# ETHERNET.net
KiCad netlist of a schematic drawn in Altium Designer
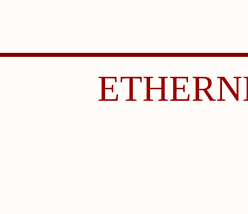
[diagram p0: ETHERNET.SchDoc, top left]
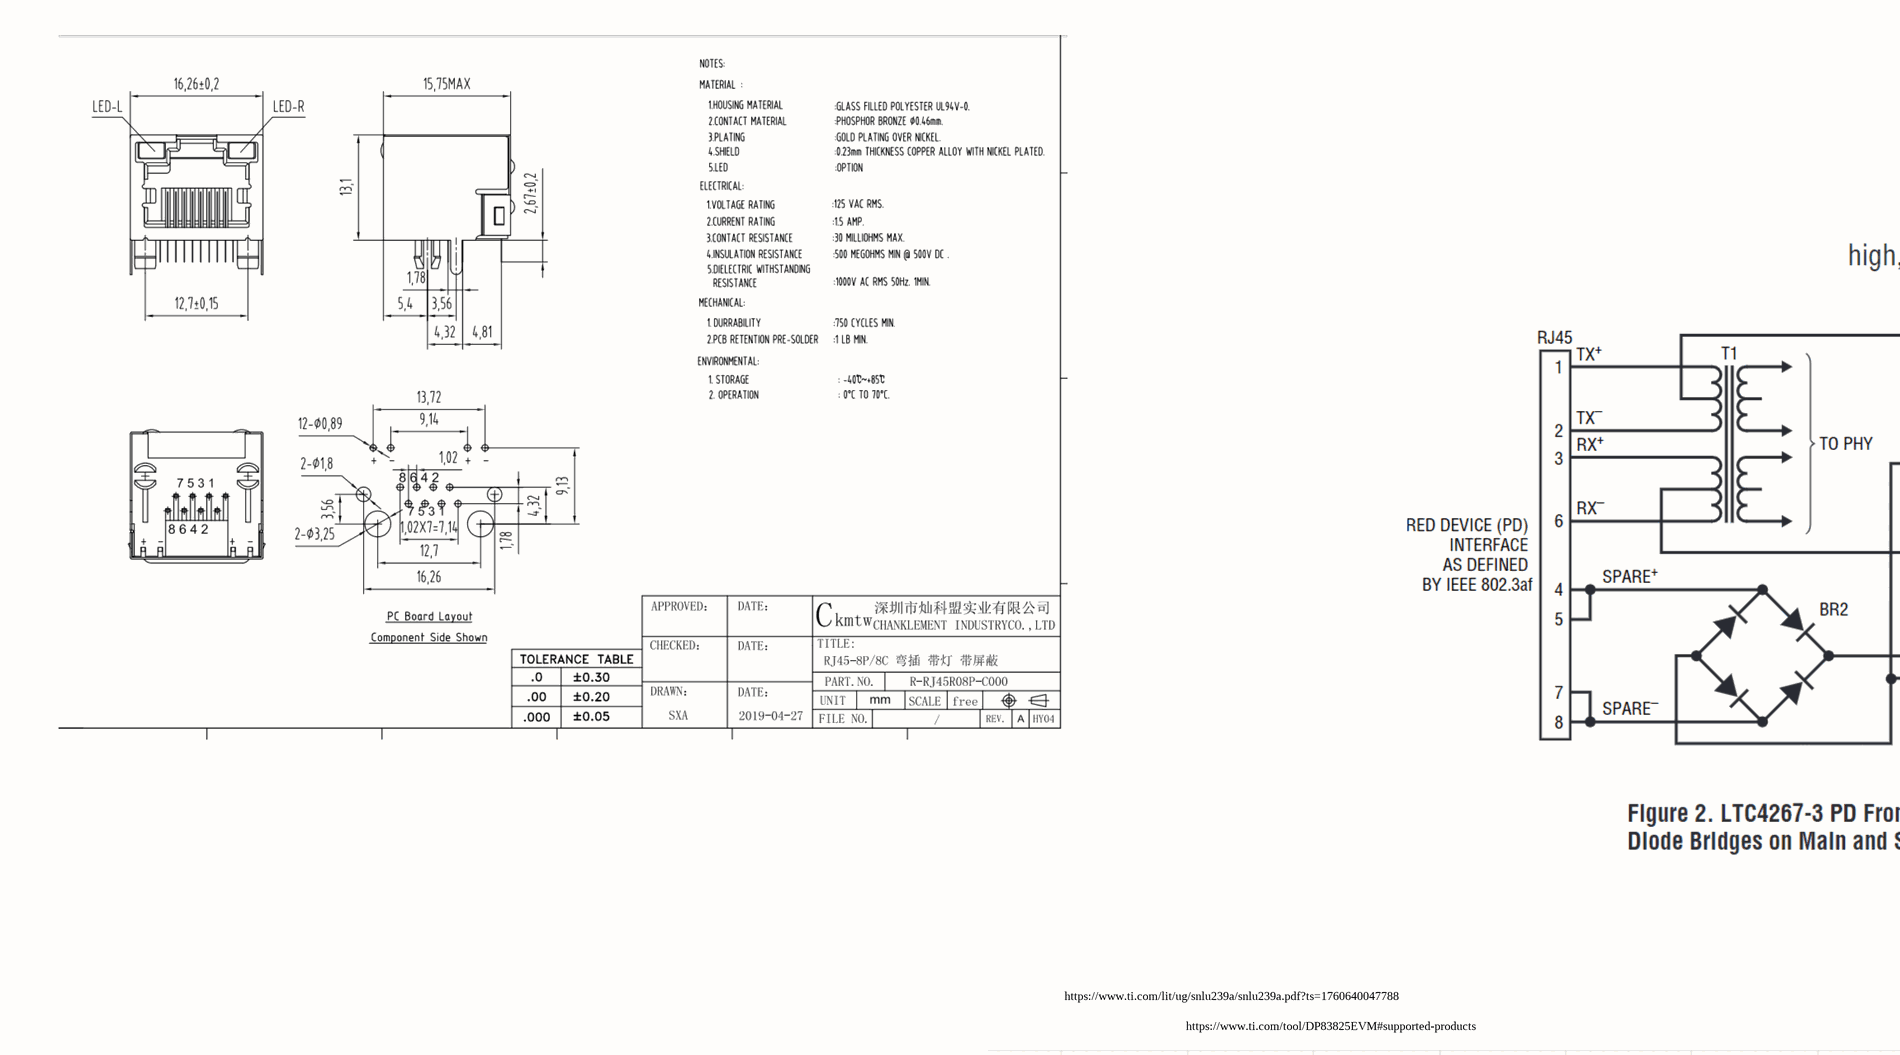
[diagram p1: ETHERNET.SchDoc, top middle]
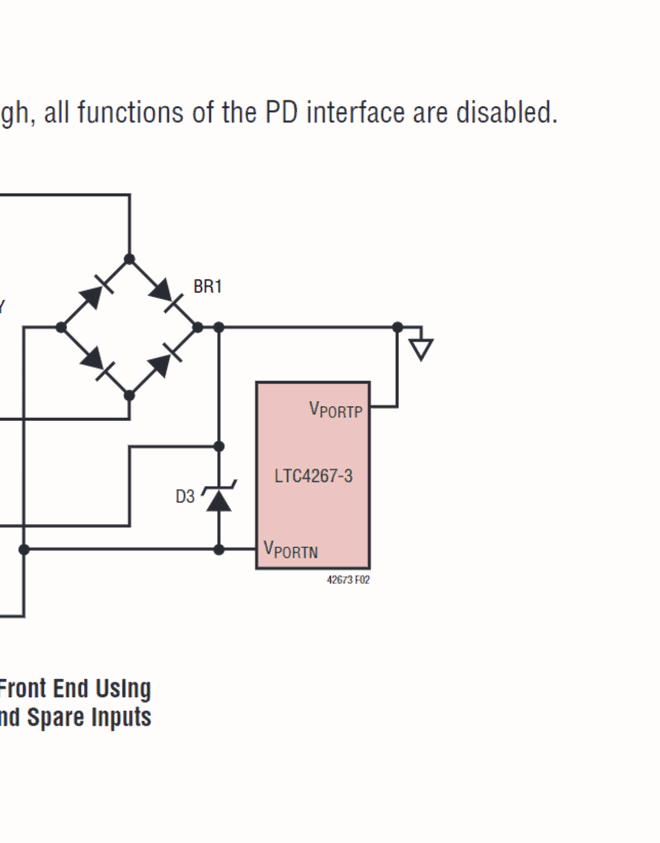
[diagram p2: ETHERNET.SchDoc, top right]
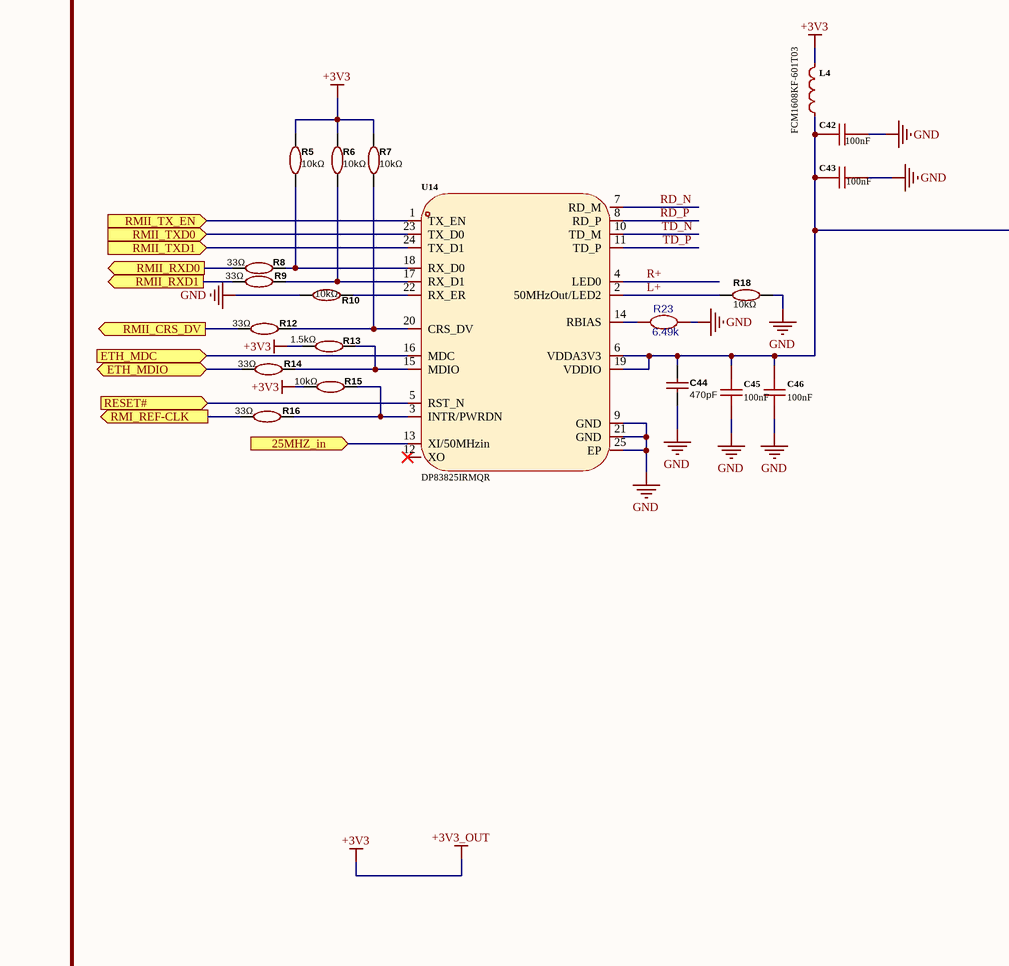
[diagram p3: ETHERNET.SchDoc, centre left]
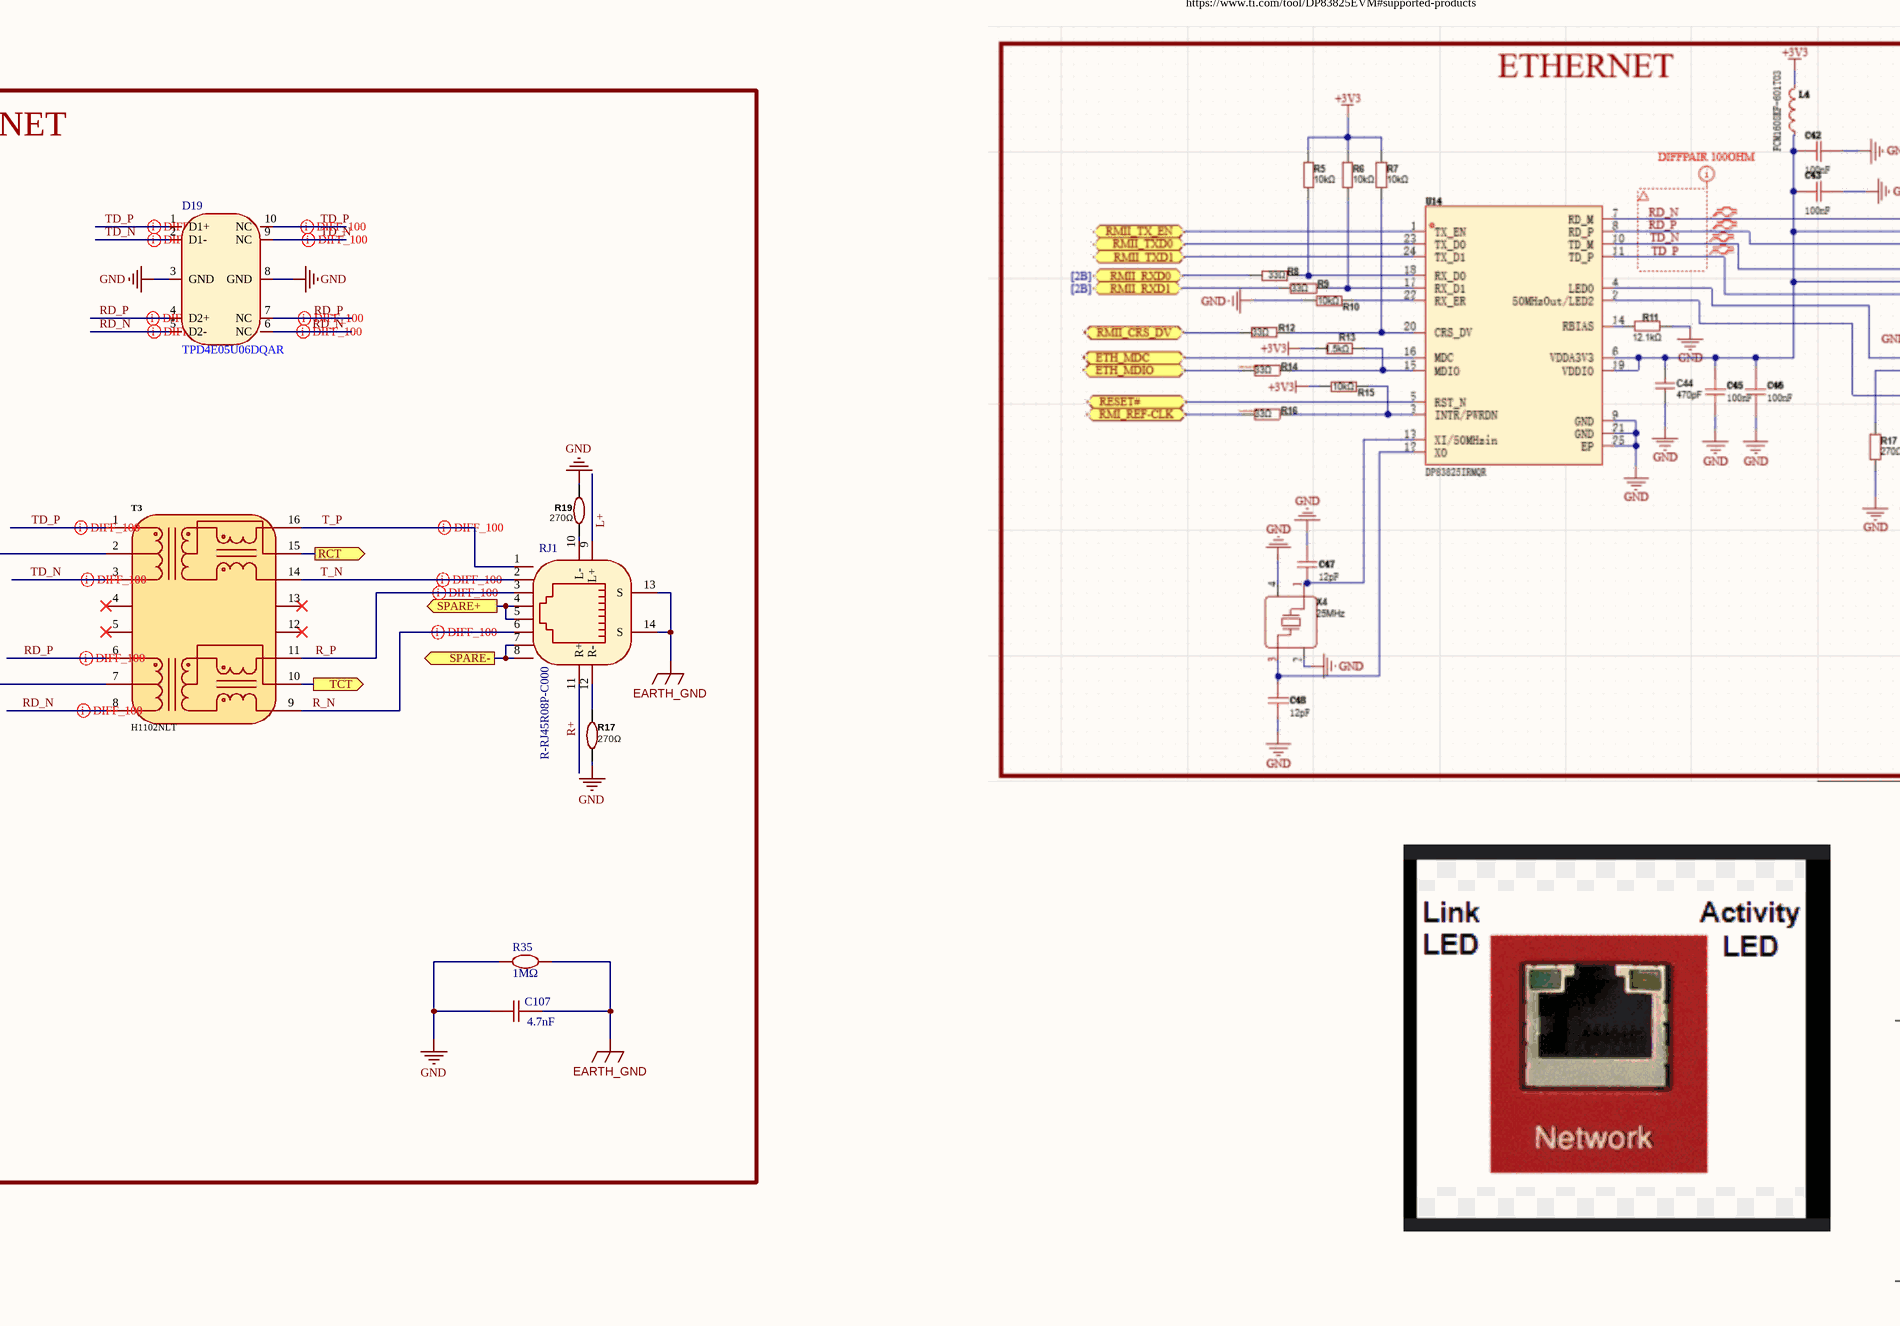
[diagram p4: ETHERNET.SchDoc, centre middle]
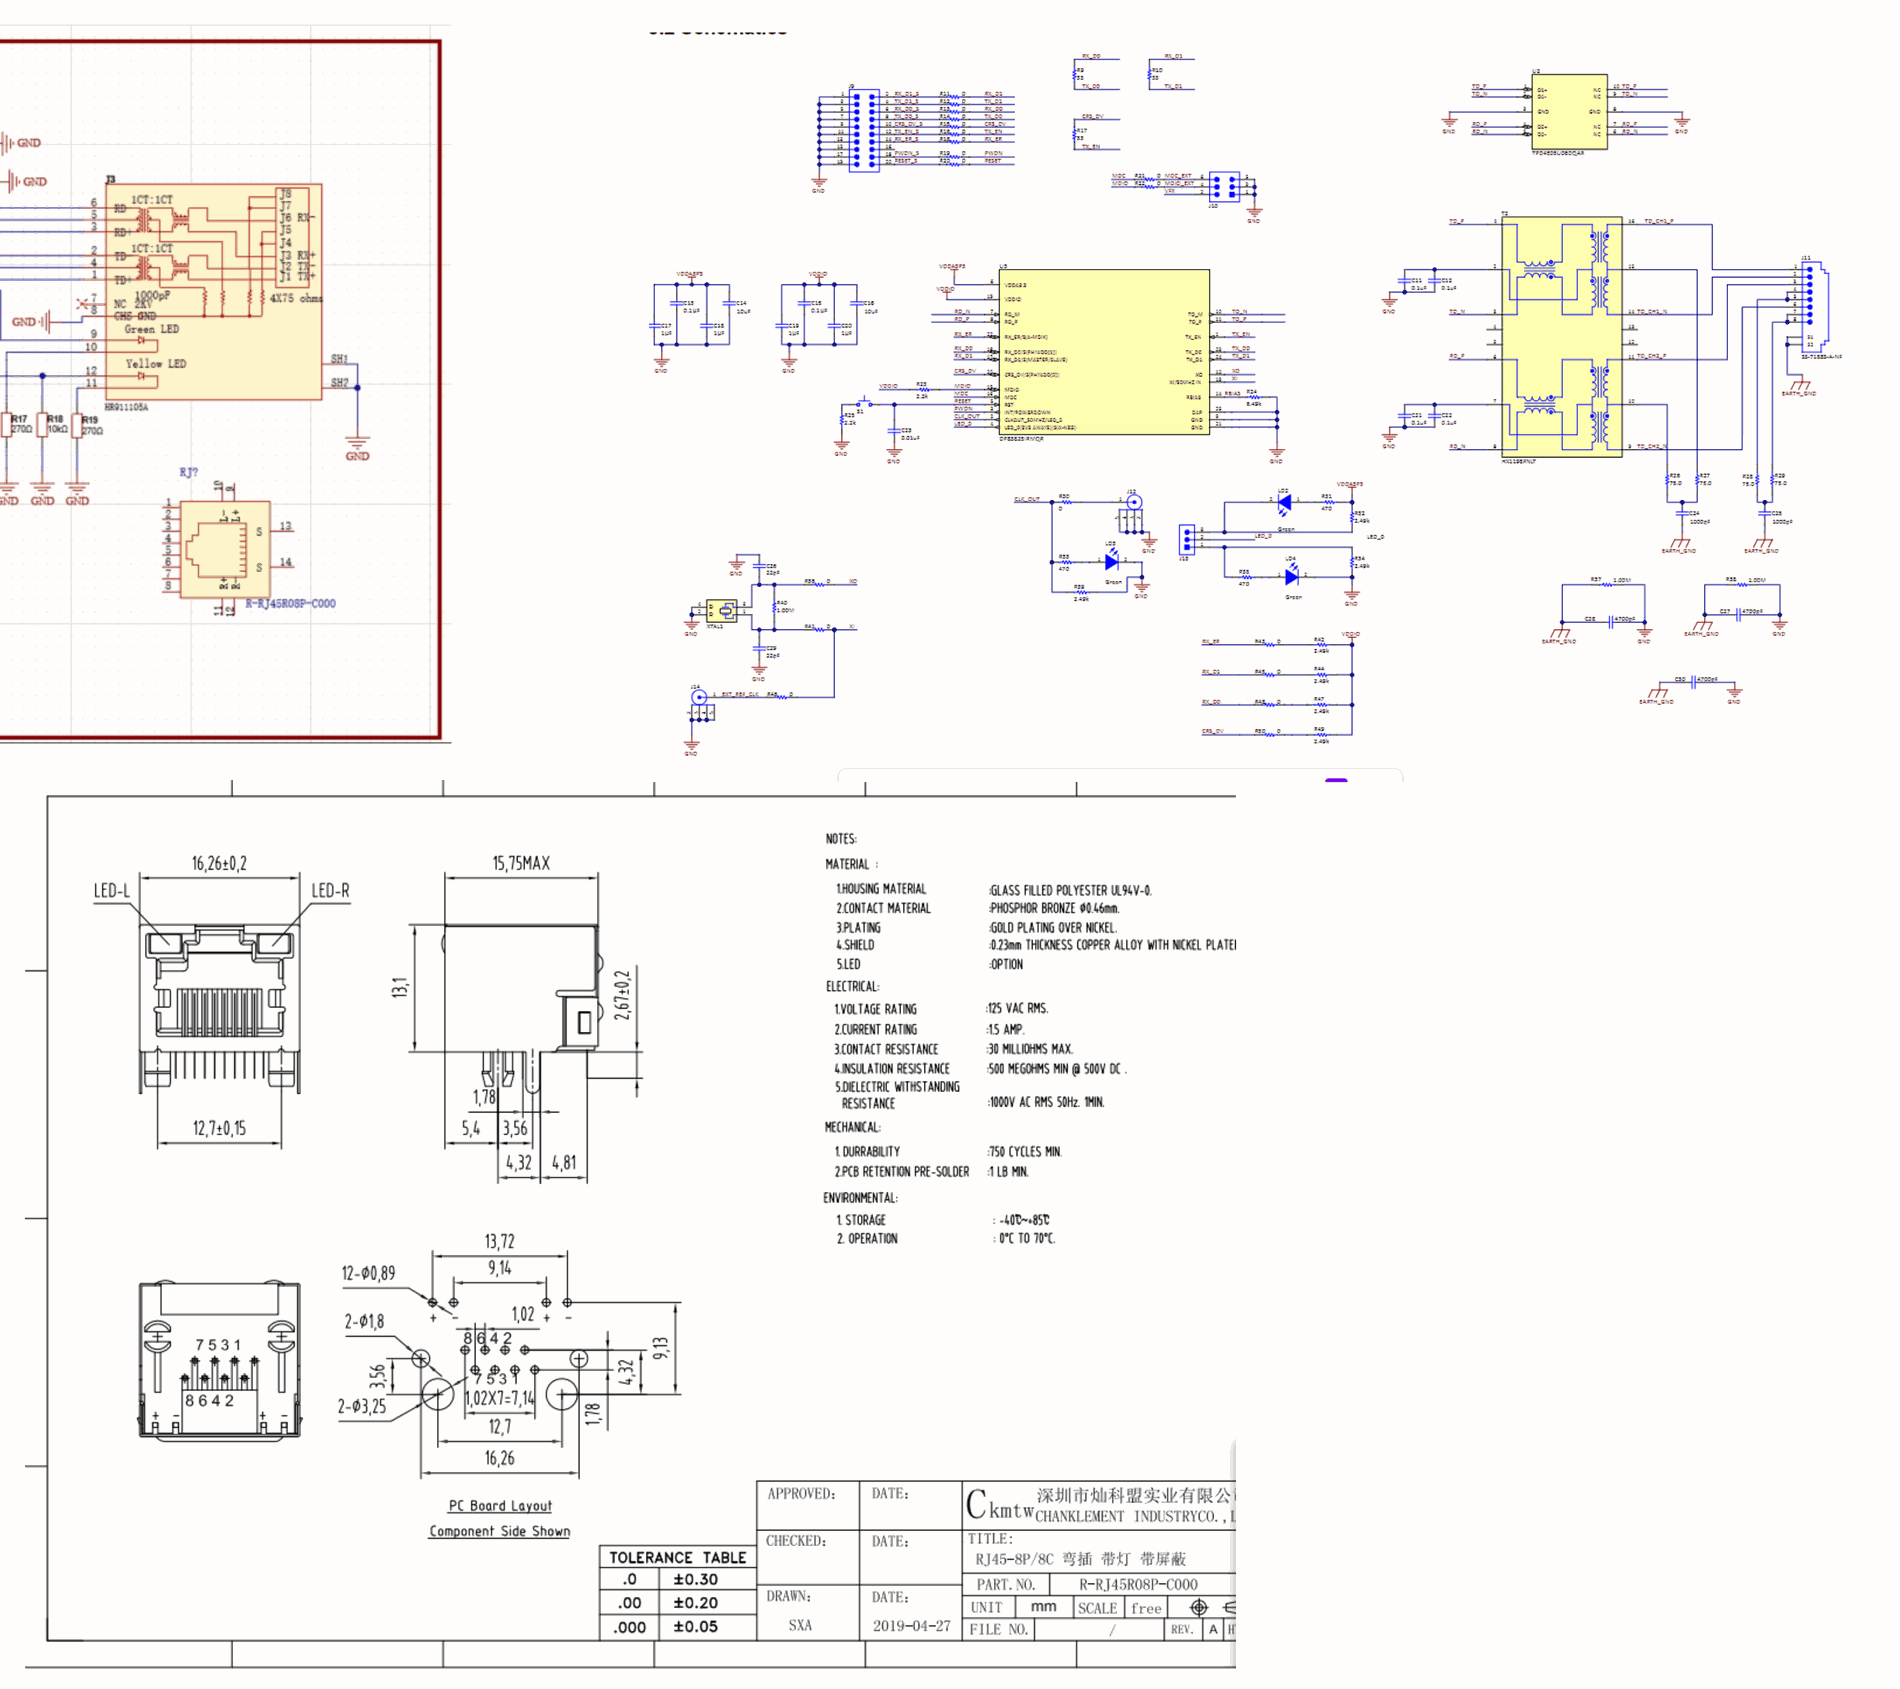
[diagram p5: ETHERNET.SchDoc, centre right]
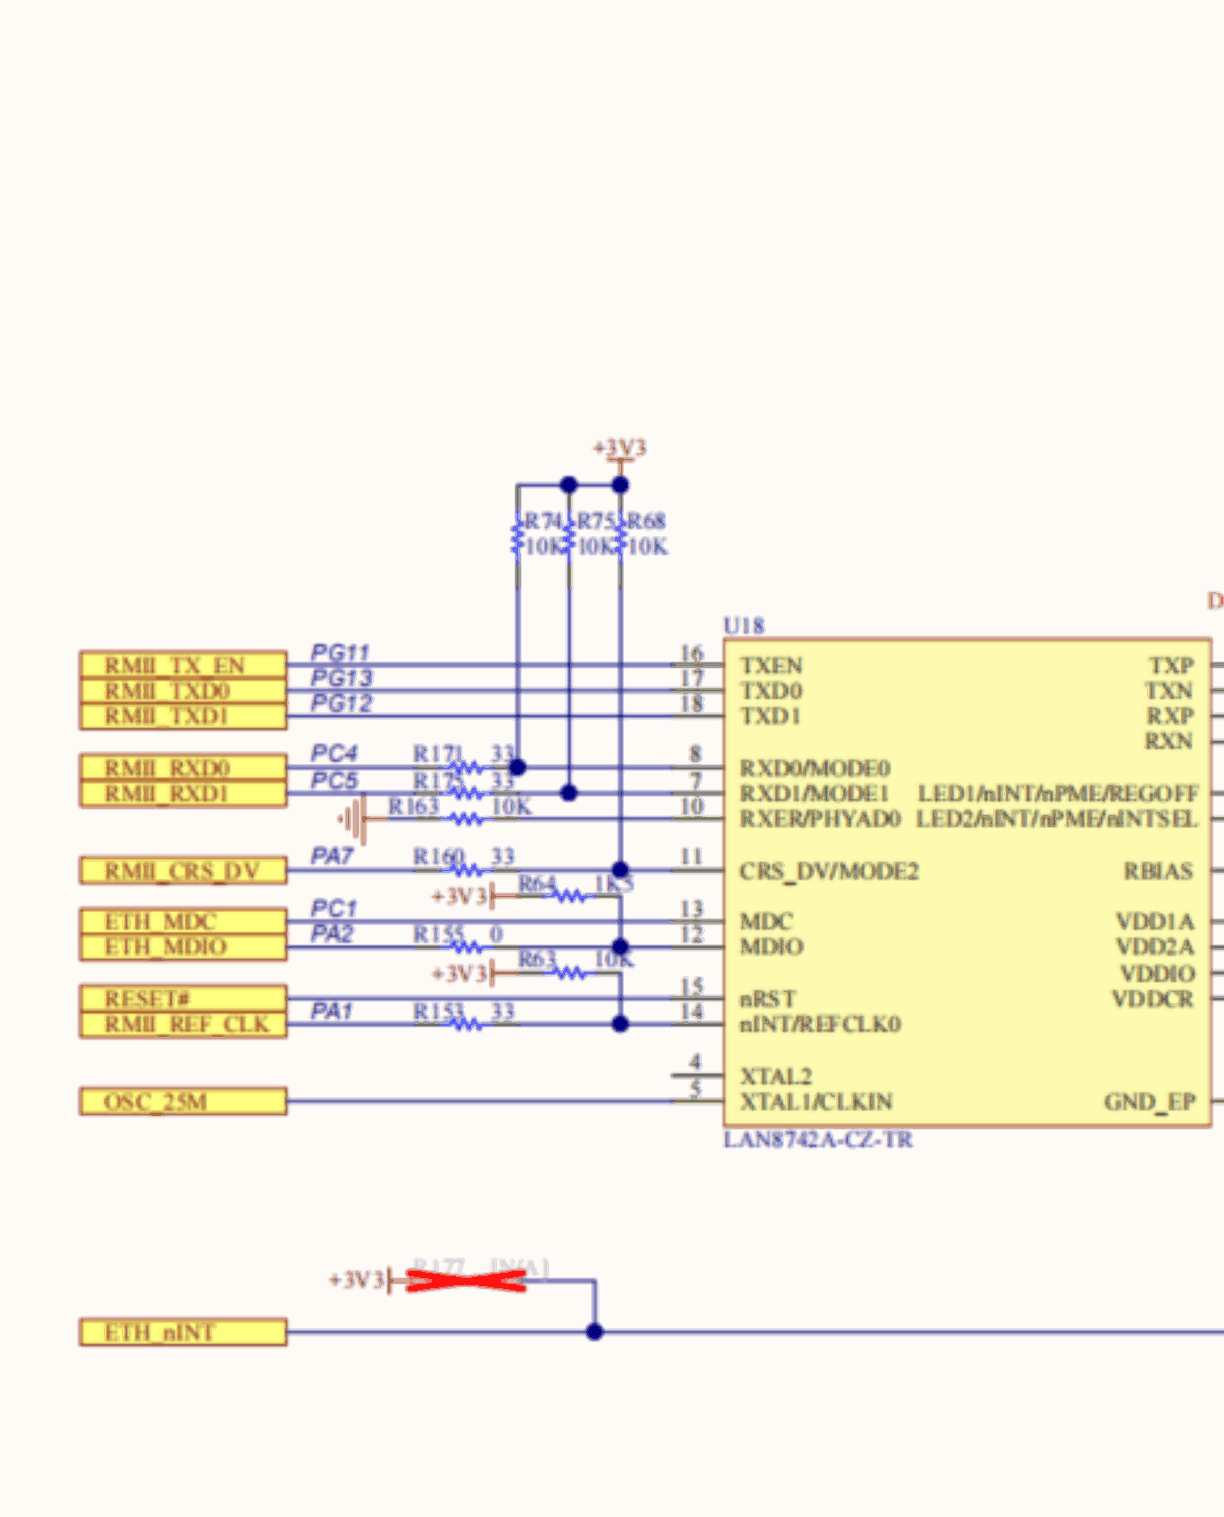
[diagram p6: ETHERNET.SchDoc, bottom left]
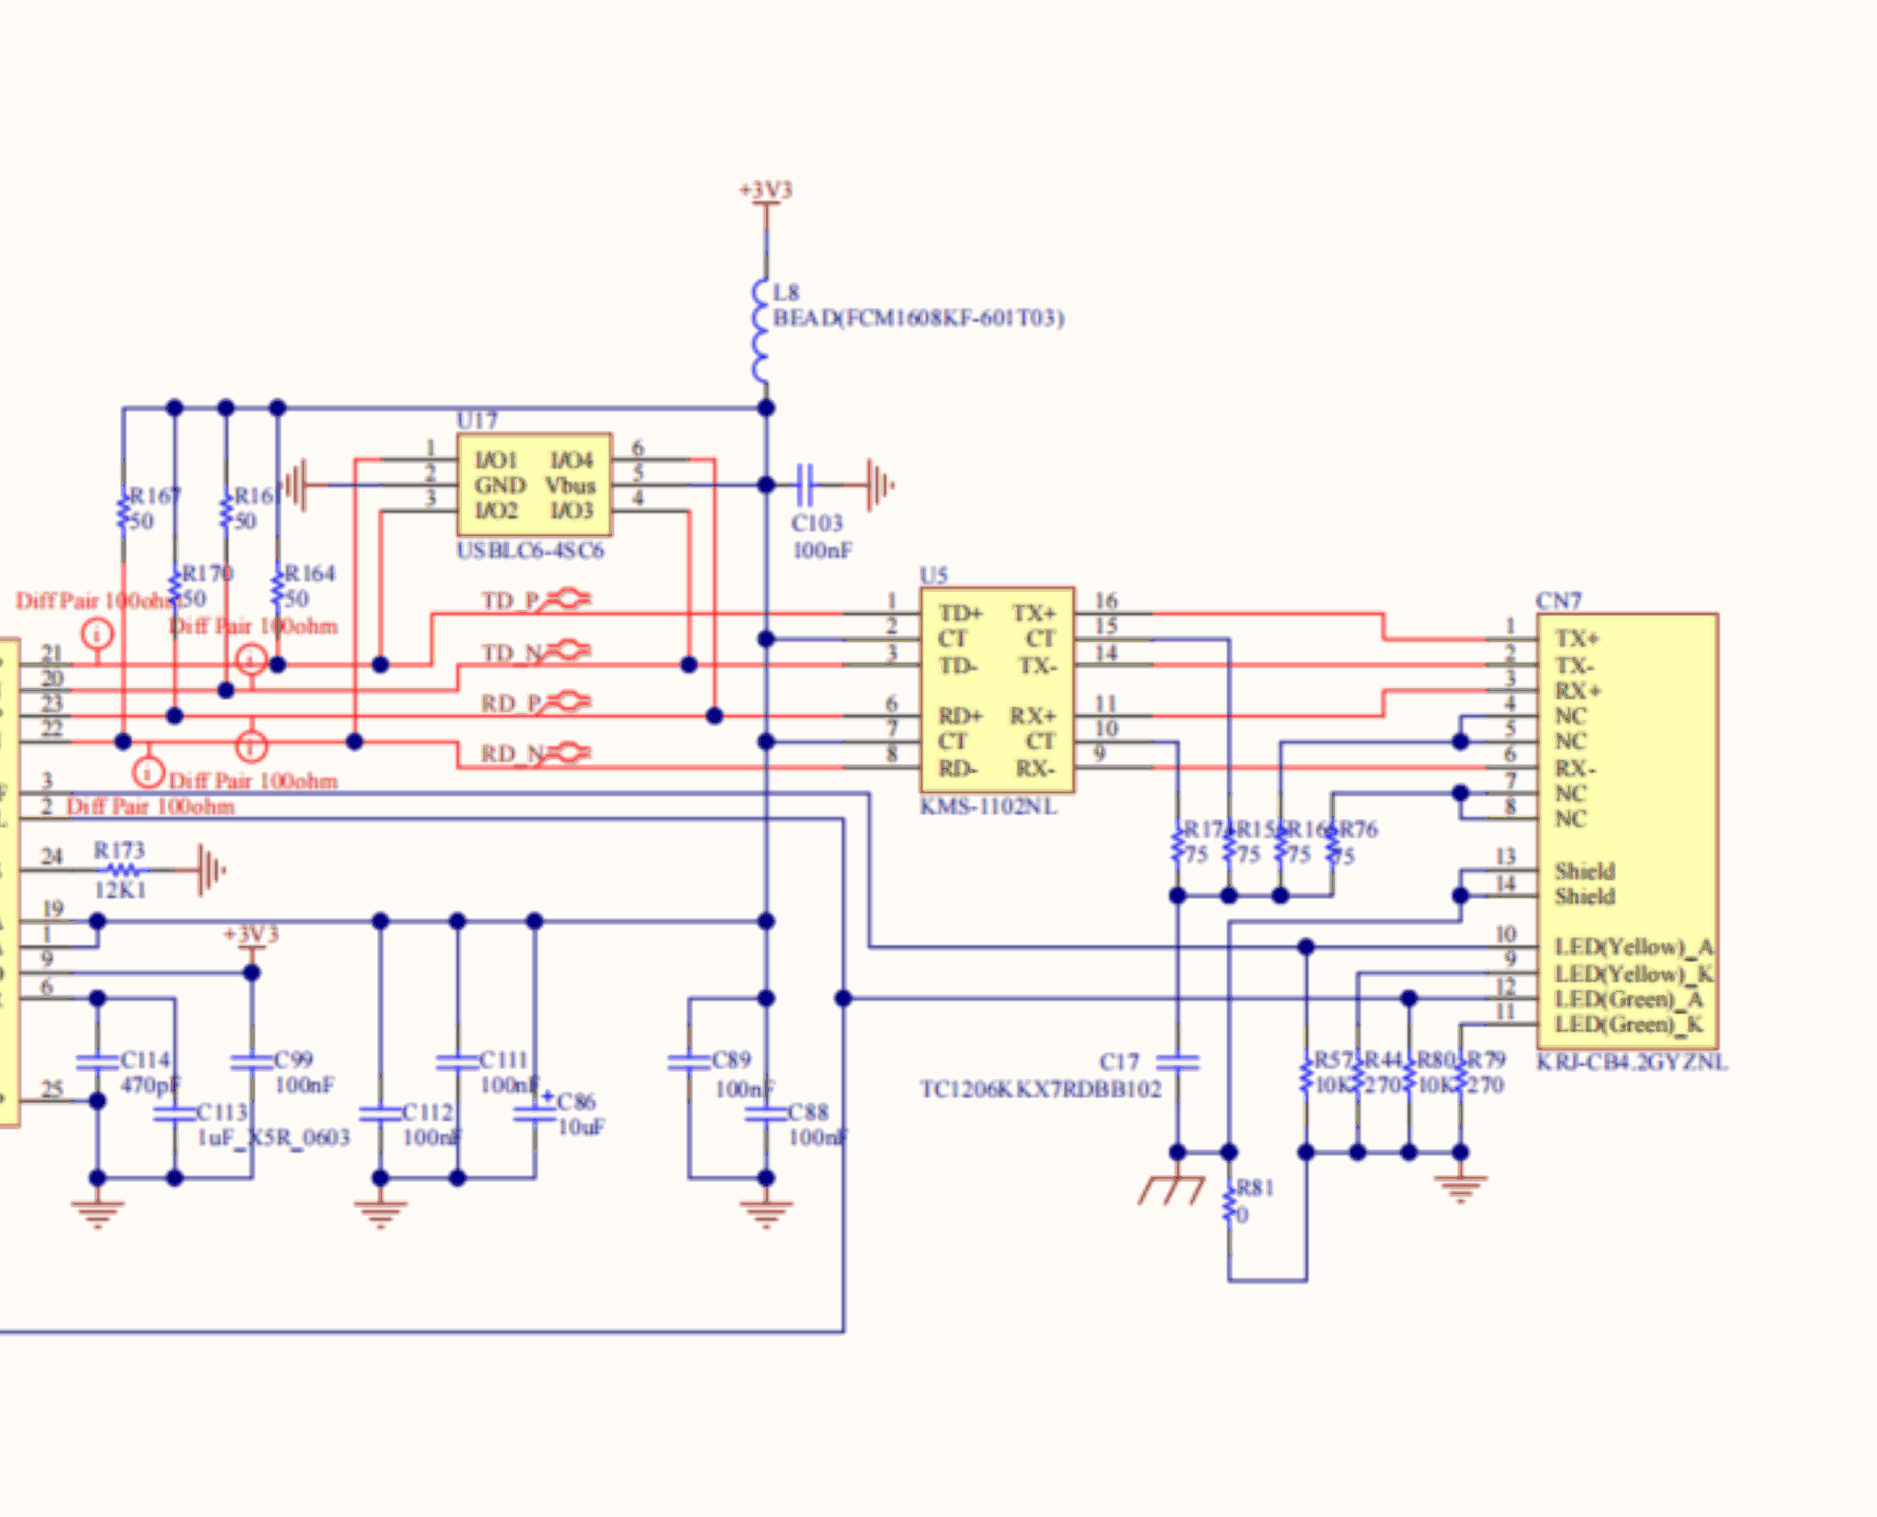
[diagram p7: ETHERNET.SchDoc, bottom middle]

(export (version "E")
  (design (tool "Eeschema 10.0.6"))
  (components
    (comp (ref "C42")
      (value "100nF")
      (footprint "C_0603")
      (fields
        (field (name "MANUFACTURER") "YAGEO(国巨)")
        (field (name "MANUFACTURER PART") "CC0603KRX7R9BB104")
        (field (name "TOLERANCE") "±10%")
      )
      (libsource (lib "altium-import") (part "root_0_CC0603KRX7R9BB104_"))
    )
    (comp (ref "C43")
      (value "100nF")
      (footprint "C_0603")
      (fields
        (field (name "MANUFACTURER") "YAGEO(国巨)")
        (field (name "MANUFACTURER PART") "CC0603KRX7R9BB104")
        (field (name "TOLERANCE") "±10%")
      )
      (libsource (lib "altium-import") (part "root_0_CC0603KRX7R9BB104_"))
    )
    (comp (ref "C44")
      (value "470pF")
      (footprint "C_0603")
      (fields
        (field (name "MANUFACTURER") "YAGEO(国巨)")
        (field (name "MANUFACTURER PART") "CC0603KRX7R9BB471")
      )
      (libsource (lib "altium-import") (part "root_1_470pF_"))
    )
    (comp (ref "C45")
      (value "100nF")
      (footprint "C_0603")
      (fields
        (field (name "MANUFACTURER") "YAGEO(国巨)")
        (field (name "MANUFACTURER PART") "CC0603KRX7R9BB104")
        (field (name "TOLERANCE") "±10%")
      )
      (libsource (lib "altium-import") (part "root_3_CC0603KRX7R9BB104_"))
    )
    (comp (ref "C46")
      (value "100nF")
      (footprint "C_0603")
      (fields
        (field (name "MANUFACTURER") "YAGEO(国巨)")
        (field (name "MANUFACTURER PART") "CC0603KRX7R9BB104")
        (field (name "TOLERANCE") "±10%")
      )
      (libsource (lib "altium-import") (part "root_3_CC0603KRX7R9BB104_"))
    )
    (comp (ref "C107")
      (value "4.7nF")
      (footprint "C1812")
      (fields
        (field (name "MANUFACTURER") "YAGEO(国巨)")
        (field (name "MANUFACTURER PART") "CC1812KKX7RDBB472")
        (field (name "TOLERANCE") "±10%")
      )
      (libsource (lib "altium-import") (part "root_0_CC1812KKX7RDBB472_"))
    )
    (comp (ref "D19")
      (value "TPD4E05U06DQAR")
      (footprint "USON-10_L2.5-W1.0-P0.50-BL")
      (fields (field (name "MANUFACTURER") "TI(德州仪器)"))
      (libsource (lib "EsoCore_Edge_Board_V1-0.0.0") (part "TPD4E05U06DQAR_C138714"))
    )
    (comp (ref "L4")
      (value "FCM1608KF-601T03")
      (footprint "R_0603")
      (fields (field (name "MANUFACTURER") "TAI-TECH(台庆)") (field (name "TOLERANCE") "±25%"))
      (libsource (lib "altium-import") (part "root_1_FCM1608KF-601T03_"))
    )
    (comp (ref "R5")
      (value "10kΩ")
      (footprint "R_0603")
      (fields (field (name "MANUFACTURER") "YAGEO(国巨)") (field (name "MANUFACTURER PART") "RC0603FR-0710KL"))
      (libsource (lib "altium-import") (part "root_3_mirrored_10kΩ_"))
    )
    (comp (ref "R6")
      (value "10kΩ")
      (footprint "R_0603")
      (fields (field (name "MANUFACTURER") "YAGEO(国巨)") (field (name "MANUFACTURER PART") "RC0603FR-0710KL"))
      (libsource (lib "altium-import") (part "root_3_mirrored_10kΩ_"))
    )
    (comp (ref "R7")
      (value "10kΩ")
      (footprint "R_0603")
      (fields (field (name "MANUFACTURER") "YAGEO(国巨)") (field (name "MANUFACTURER PART") "RC0603FR-0710KL"))
      (libsource (lib "altium-import") (part "root_3_mirrored_10kΩ_"))
    )
    (comp (ref "R8")
      (value "33Ω")
      (footprint "R_0603")
      (fields (field (name "MANUFACTURER") "YAGEO(国巨)") (field (name "MANUFACTURER PART") "RC0603FR-0733RL"))
      (libsource (lib "altium-import") (part "root_0_33Ω_"))
    )
    (comp (ref "R9")
      (value "33Ω")
      (footprint "R_0603")
      (fields (field (name "MANUFACTURER") "YAGEO(国巨)") (field (name "MANUFACTURER PART") "RC0603FR-0733RL"))
      (libsource (lib "altium-import") (part "root_0_33Ω_"))
    )
    (comp (ref "R10")
      (value "10kΩ")
      (footprint "R_0603")
      (fields (field (name "MANUFACTURER") "YAGEO(国巨)") (field (name "MANUFACTURER PART") "RC0603FR-0710KL"))
      (libsource (lib "altium-import") (part "root_0_mirrored_10kΩ_"))
    )
    (comp (ref "R12")
      (value "33Ω")
      (footprint "R_0603")
      (fields (field (name "MANUFACTURER") "YAGEO(国巨)") (field (name "MANUFACTURER PART") "RC0603FR-0733RL"))
      (libsource (lib "altium-import") (part "root_0_33Ω_"))
    )
    (comp (ref "R13")
      (value "1.5kΩ")
      (footprint "R_0603")
      (fields
        (field (name "MANUFACTURER") "UNI-ROYAL(厚声)")
        (field (name "MANUFACTURER PART") "0603WAF1501T5E")
      )
      (libsource (lib "altium-import") (part "root_0_1.5kΩ_"))
    )
    (comp (ref "R14")
      (value "33Ω")
      (footprint "R_0603")
      (fields (field (name "MANUFACTURER") "YAGEO(国巨)") (field (name "MANUFACTURER PART") "RC0603FR-0733RL"))
      (libsource (lib "altium-import") (part "root_0_33Ω_"))
    )
    (comp (ref "R15")
      (value "10kΩ")
      (footprint "R_0603")
      (fields (field (name "MANUFACTURER") "YAGEO(国巨)") (field (name "MANUFACTURER PART") "RC0603FR-0710KL"))
      (libsource (lib "altium-import") (part "root_0_mirrored_10kΩ_"))
    )
    (comp (ref "R16")
      (value "33Ω")
      (footprint "R_0603")
      (fields (field (name "MANUFACTURER") "YAGEO(国巨)") (field (name "MANUFACTURER PART") "RC0603FR-0733RL"))
      (libsource (lib "altium-import") (part "root_0_33Ω_"))
    )
    (comp (ref "R17")
      (value "270Ω")
      (footprint "R_0603")
      (fields (field (name "MANUFACTURER") "YAGEO(国巨)") (field (name "MANUFACTURER PART") "RC0603FR-07270RL"))
      (libsource (lib "altium-import") (part "root_1_270Ω_"))
    )
    (comp (ref "R18")
      (value "10kΩ")
      (footprint "R_0603")
      (fields (field (name "MANUFACTURER") "YAGEO(国巨)") (field (name "MANUFACTURER PART") "RC0603FR-0710KL"))
      (libsource (lib "altium-import") (part "root_0_mirrored_10kΩ_"))
    )
    (comp (ref "R19")
      (value "270Ω")
      (footprint "R_0603")
      (fields (field (name "MANUFACTURER") "YAGEO(国巨)") (field (name "MANUFACTURER PART") "RC0603FR-07270RL"))
      (libsource (lib "altium-import") (part "root_3_270Ω_"))
    )
    (comp (ref "R23")
      (value "6.49k")
      (footprint "R_0603")
      (fields
        (field (name "MANUFACTURER") "YAGEO(国巨)")
        (field (name "MANUFACTURER PART") "RT0603BRC076K49L")
        (field (name "CONTRIBUTOR") "lcsc")
      )
      (libsource (lib "altium-import") (part "root_0_6.49kΩ_"))
    )
    (comp (ref "R35")
      (value "1MΩ")
      (footprint "R2010")
      (fields
        (field (name "MANUFACTURER") "VISHAY(威世)")
        (field (name "MANUFACTURER PART") "RCV20101M00FKEFAT")
        (field (name "TOLERANCE") "±1%")
      )
      (libsource (lib "altium-import") (part "root_0_RCV20101M00FKEFAT_"))
    )
    (comp (ref "RJ1")
      (value "R-RJ45R08P-C000")
      (footprint "RJ45-TH_R-RJ45R08P-C000")
      (fields (field (name "MANUFACTURER") "Ckmtw(灿科盟)"))
      (libsource (lib "altium-import") (part "root_3_R-RJ45R08P-C000_"))
    )
    (comp (ref "T3")
      (value "H1102NLT")
      (footprint "XFMR-SMD_H1102NLT")
      (fields (field (name "MANUFACTURER") "DEXU(德旭电子)"))
      (libsource (lib "EsoCore_Edge_Board_V1-0.0.0") (part "H1102NLT_C20623173"))
    )
    (comp (ref "U14")
      (value "DP83825IRMQR")
      (footprint "HVQFN-24_L3.0-W3.0-P0.40-TL-EP1.9")
      (fields (field (name "MANUFACTURER") "TI(德州仪器)"))
      (libsource (lib "EsoCore_Edge_Board_V1-0.0.0") (part "DP83825IRMQR"))
    )
  )
  (nets
    (net (code "1") (name "+3V3") (class "Default")
      (node (ref "L4") (pin "2") (pinfunction "2_2") (pintype "passive"))
      (node (ref "R13") (pin "1") (pinfunction "1_1") (pintype "passive"))
      (node (ref "R15") (pin "2") (pinfunction "2_2") (pintype "passive"))
      (node (ref "R5") (pin "1") (pinfunction "1_1") (pintype "passive"))
      (node (ref "R6") (pin "1") (pinfunction "1_1") (pintype "passive"))
      (node (ref "R7") (pin "1") (pinfunction "1_1") (pintype "passive"))
    )
    (net (code "2") (name "/25MHZ_in") (class "Default")
      (node (ref "U14") (pin "13") (pinfunction "XI/50MHzin_13") (pintype "passive"))
    )
    (net (code "3") (name "/ETH_MDC") (class "Default")
      (node (ref "U14") (pin "16") (pinfunction "MDC_16") (pintype "passive"))
    )
    (net (code "4") (name "/ETH_MDIO") (class "Default")
      (node (ref "R14") (pin "1") (pinfunction "1_1") (pintype "passive"))
    )
    (net (code "5") (name "/L+") (class "Default")
      (node (ref "R18") (pin "2") (pinfunction "2_2") (pintype "passive"))
      (node (ref "RJ1") (pin "9") (pinfunction "L+_9") (pintype "passive"))
      (node (ref "U14") (pin "2") (pinfunction "50MHzOut/LED2_2") (pintype "passive"))
    )
    (net (code "6") (name "/R+") (class "Default")
      (node (ref "RJ1") (pin "11") (pinfunction "R+_11") (pintype "passive"))
      (node (ref "U14") (pin "4") (pinfunction "LED0_4") (pintype "passive"))
    )
    (net (code "7") (name "/RCT") (class "Default")
      (node (ref "T3") (pin "15") (pinfunction "15_15") (pintype "passive"))
    )
    (net (code "8") (name "/RD_N") (class "Default")
      (node (ref "D19") (pin "5") (pinfunction "D2-_5") (pintype "passive"))
      (node (ref "D19") (pin "6") (pinfunction "NC_6") (pintype "passive"))
      (node (ref "T3") (pin "8") (pinfunction "8_8") (pintype "passive"))
      (node (ref "U14") (pin "7") (pinfunction "RD_M_7") (pintype "passive"))
    )
    (net (code "9") (name "/RD_P") (class "Default")
      (node (ref "D19") (pin "4") (pinfunction "D2+_4") (pintype "passive"))
      (node (ref "D19") (pin "7") (pinfunction "NC_7") (pintype "passive"))
      (node (ref "T3") (pin "6") (pinfunction "6_6") (pintype "passive"))
      (node (ref "U14") (pin "8") (pinfunction "RD_P_8") (pintype "passive"))
    )
    (net (code "10") (name "/RESET#") (class "Default")
      (node (ref "U14") (pin "5") (pinfunction "RST_N_5") (pintype "passive"))
    )
    (net (code "11") (name "/RMII_CRS_DV") (class "Default")
      (node (ref "R12") (pin "1") (pinfunction "1_1") (pintype "passive"))
    )
    (net (code "12") (name "/RMII_RXD0") (class "Default")
      (node (ref "R8") (pin "1") (pinfunction "1_1") (pintype "passive"))
    )
    (net (code "13") (name "/RMII_RXD1") (class "Default")
      (node (ref "R9") (pin "1") (pinfunction "1_1") (pintype "passive"))
    )
    (net (code "14") (name "/RMII_TXD0") (class "Default")
      (node (ref "U14") (pin "23") (pinfunction "TX_D0_23") (pintype "passive"))
    )
    (net (code "15") (name "/RMII_TXD1") (class "Default")
      (node (ref "U14") (pin "24") (pinfunction "TX_D1_24") (pintype "passive"))
    )
    (net (code "16") (name "/RMII_TX_EN") (class "Default")
      (node (ref "U14") (pin "1") (pinfunction "TX_EN_1") (pintype "passive"))
    )
    (net (code "17") (name "/RMI_REF-CLK") (class "Default")
      (node (ref "R16") (pin "1") (pinfunction "1_1") (pintype "passive"))
    )
    (net (code "18") (name "/R_N") (class "Default")
      (node (ref "RJ1") (pin "6") (pinfunction "6_6") (pintype "passive"))
      (node (ref "T3") (pin "9") (pinfunction "9_9") (pintype "passive"))
    )
    (net (code "19") (name "/R_P") (class "Default")
      (node (ref "RJ1") (pin "3") (pinfunction "3_3") (pintype "passive"))
      (node (ref "T3") (pin "11") (pinfunction "11_11") (pintype "passive"))
    )
    (net (code "20") (name "/SPARE+") (class "Default")
      (node (ref "RJ1") (pin "4") (pinfunction "4_4") (pintype "passive"))
      (node (ref "RJ1") (pin "5") (pinfunction "5_5") (pintype "passive"))
    )
    (net (code "21") (name "/SPARE-") (class "Default")
      (node (ref "RJ1") (pin "7") (pinfunction "7_7") (pintype "passive"))
      (node (ref "RJ1") (pin "8") (pinfunction "8_8") (pintype "passive"))
    )
    (net (code "22") (name "/TCT") (class "Default")
      (node (ref "T3") (pin "10") (pinfunction "10_10") (pintype "passive"))
    )
    (net (code "23") (name "/TD_N") (class "Default")
      (node (ref "D19") (pin "2") (pinfunction "D1-_2") (pintype "passive"))
      (node (ref "D19") (pin "9") (pinfunction "NC_9") (pintype "passive"))
      (node (ref "T3") (pin "3") (pinfunction "3_3") (pintype "passive"))
      (node (ref "U14") (pin "10") (pinfunction "TD_M_10") (pintype "passive"))
    )
    (net (code "24") (name "/TD_P") (class "Default")
      (node (ref "D19") (pin "1") (pinfunction "D1+_1") (pintype "passive"))
      (node (ref "D19") (pin "10") (pinfunction "NC_10") (pintype "passive"))
      (node (ref "T3") (pin "1") (pinfunction "1_1") (pintype "passive"))
      (node (ref "U14") (pin "11") (pinfunction "TD_P_11") (pintype "passive"))
    )
    (net (code "25") (name "/T_N") (class "Default")
      (node (ref "RJ1") (pin "2") (pinfunction "2_2") (pintype "passive"))
      (node (ref "T3") (pin "14") (pinfunction "14_14") (pintype "passive"))
    )
    (net (code "26") (name "/T_P") (class "Default")
      (node (ref "RJ1") (pin "1") (pinfunction "1_1") (pintype "passive"))
      (node (ref "T3") (pin "16") (pinfunction "16_16") (pintype "passive"))
    )
    (net (code "27") (name "EARTH_GND") (class "Default")
      (node (ref "C107") (pin "1") (pinfunction "1_1") (pintype "passive"))
      (node (ref "R35") (pin "2") (pinfunction "2_2") (pintype "passive"))
      (node (ref "RJ1") (pin "13") (pinfunction "S_13") (pintype "passive"))
      (node (ref "RJ1") (pin "14") (pinfunction "S_14") (pintype "passive"))
    )
    (net (code "28") (name "GND") (class "Default")
      (node (ref "C107") (pin "2") (pinfunction "2_2") (pintype "passive"))
      (node (ref "C42") (pin "2") (pinfunction "2_2") (pintype "passive"))
      (node (ref "C43") (pin "2") (pinfunction "2_2") (pintype "passive"))
      (node (ref "C44") (pin "1") (pinfunction "1_1") (pintype "passive"))
      (node (ref "C45") (pin "2") (pinfunction "2_2") (pintype "passive"))
      (node (ref "C46") (pin "2") (pinfunction "2_2") (pintype "passive"))
      (node (ref "D19") (pin "3") (pinfunction "GND_3") (pintype "passive"))
      (node (ref "D19") (pin "8") (pinfunction "GND_8") (pintype "passive"))
      (node (ref "R10") (pin "2") (pinfunction "2_2") (pintype "passive"))
      (node (ref "R17") (pin "1") (pinfunction "1_1") (pintype "passive"))
      (node (ref "R18") (pin "1") (pinfunction "1_1") (pintype "passive"))
      (node (ref "R19") (pin "1") (pinfunction "1_1") (pintype "passive"))
      (node (ref "R23") (pin "2") (pinfunction "2_2") (pintype "passive"))
      (node (ref "R35") (pin "1") (pinfunction "1_1") (pintype "passive"))
      (node (ref "U14") (pin "21") (pinfunction "GND_21") (pintype "passive"))
      (node (ref "U14") (pin "25") (pinfunction "EP_25") (pintype "passive"))
      (node (ref "U14") (pin "9") (pinfunction "GND_9") (pintype "passive"))
    )
    (net (code "29") (name "Net-(RJ1-L-)") (class "Default")
      (node (ref "R19") (pin "2") (pinfunction "2_2") (pintype "passive"))
      (node (ref "RJ1") (pin "10") (pinfunction "L-_10") (pintype "passive"))
    )
    (net (code "30") (name "Net-(RJ1-R-)") (class "Default")
      (node (ref "R17") (pin "2") (pinfunction "2_2") (pintype "passive"))
      (node (ref "RJ1") (pin "12") (pinfunction "R-_12") (pintype "passive"))
    )
    (net (code "31") (name "Net-(U14-CRS_DV)") (class "Default")
      (node (ref "R12") (pin "2") (pinfunction "2_2") (pintype "passive"))
      (node (ref "R7") (pin "2") (pinfunction "2_2") (pintype "passive"))
      (node (ref "U14") (pin "20") (pinfunction "CRS_DV_20") (pintype "passive"))
    )
    (net (code "32") (name "Net-(U14-INTR{slash}PWRDN)") (class "Default")
      (node (ref "R15") (pin "1") (pinfunction "1_1") (pintype "passive"))
      (node (ref "R16") (pin "2") (pinfunction "2_2") (pintype "passive"))
      (node (ref "U14") (pin "3") (pinfunction "INTR/PWRDN_3") (pintype "passive"))
    )
    (net (code "33") (name "Net-(U14-MDIO)") (class "Default")
      (node (ref "R13") (pin "2") (pinfunction "2_2") (pintype "passive"))
      (node (ref "R14") (pin "2") (pinfunction "2_2") (pintype "passive"))
      (node (ref "U14") (pin "15") (pinfunction "MDIO_15") (pintype "passive"))
    )
    (net (code "34") (name "Net-(U14-RBIAS)") (class "Default")
      (node (ref "R23") (pin "1") (pinfunction "1_1") (pintype "passive"))
      (node (ref "U14") (pin "14") (pinfunction "RBIAS_14") (pintype "passive"))
    )
    (net (code "35") (name "Net-(U14-RX_D0)") (class "Default")
      (node (ref "R5") (pin "2") (pinfunction "2_2") (pintype "passive"))
      (node (ref "R8") (pin "2") (pinfunction "2_2") (pintype "passive"))
      (node (ref "U14") (pin "18") (pinfunction "RX_D0_18") (pintype "passive"))
    )
    (net (code "36") (name "Net-(U14-RX_D1)") (class "Default")
      (node (ref "R6") (pin "2") (pinfunction "2_2") (pintype "passive"))
      (node (ref "R9") (pin "2") (pinfunction "2_2") (pintype "passive"))
      (node (ref "U14") (pin "17") (pinfunction "RX_D1_17") (pintype "passive"))
    )
    (net (code "37") (name "Net-(U14-RX_ER)") (class "Default")
      (node (ref "R10") (pin "1") (pinfunction "1_1") (pintype "passive"))
      (node (ref "U14") (pin "22") (pinfunction "RX_ER_22") (pintype "passive"))
    )
    (net (code "38") (name "Net-(U14-VDDA3V3)") (class "Default")
      (node (ref "C42") (pin "1") (pinfunction "1_1") (pintype "passive"))
      (node (ref "C43") (pin "1") (pinfunction "1_1") (pintype "passive"))
      (node (ref "C44") (pin "2") (pinfunction "2_2") (pintype "passive"))
      (node (ref "C45") (pin "1") (pinfunction "1_1") (pintype "passive"))
      (node (ref "C46") (pin "1") (pinfunction "1_1") (pintype "passive"))
      (node (ref "L4") (pin "1") (pinfunction "1_1") (pintype "passive"))
      (node (ref "T3") (pin "2") (pinfunction "2_2") (pintype "passive"))
      (node (ref "T3") (pin "7") (pinfunction "7_7") (pintype "passive"))
      (node (ref "U14") (pin "19") (pinfunction "VDDIO_19") (pintype "passive"))
      (node (ref "U14") (pin "6") (pinfunction "VDDA3V3_6") (pintype "passive"))
    )
    (net (code "39") (name "unconnected-(T3-Pad4)") (class "Default")
      (node (ref "T3") (pin "4") (pinfunction "4_4") (pintype "passive+no_connect"))
    )
    (net (code "40") (name "unconnected-(T3-Pad5)") (class "Default")
      (node (ref "T3") (pin "5") (pinfunction "5_5") (pintype "passive+no_connect"))
    )
    (net (code "41") (name "unconnected-(T3-Pad12)") (class "Default")
      (node (ref "T3") (pin "12") (pinfunction "12_12") (pintype "passive+no_connect"))
    )
    (net (code "42") (name "unconnected-(T3-Pad13)") (class "Default")
      (node (ref "T3") (pin "13") (pinfunction "13_13") (pintype "passive+no_connect"))
    )
    (net (code "43") (name "unconnected-(U14-XO-Pad12)") (class "Default")
      (node (ref "U14") (pin "12") (pinfunction "XO_12") (pintype "passive+no_connect"))
    )
  )
)
